# Power.net
KiCad netlist of a schematic drawn in Altium Designer
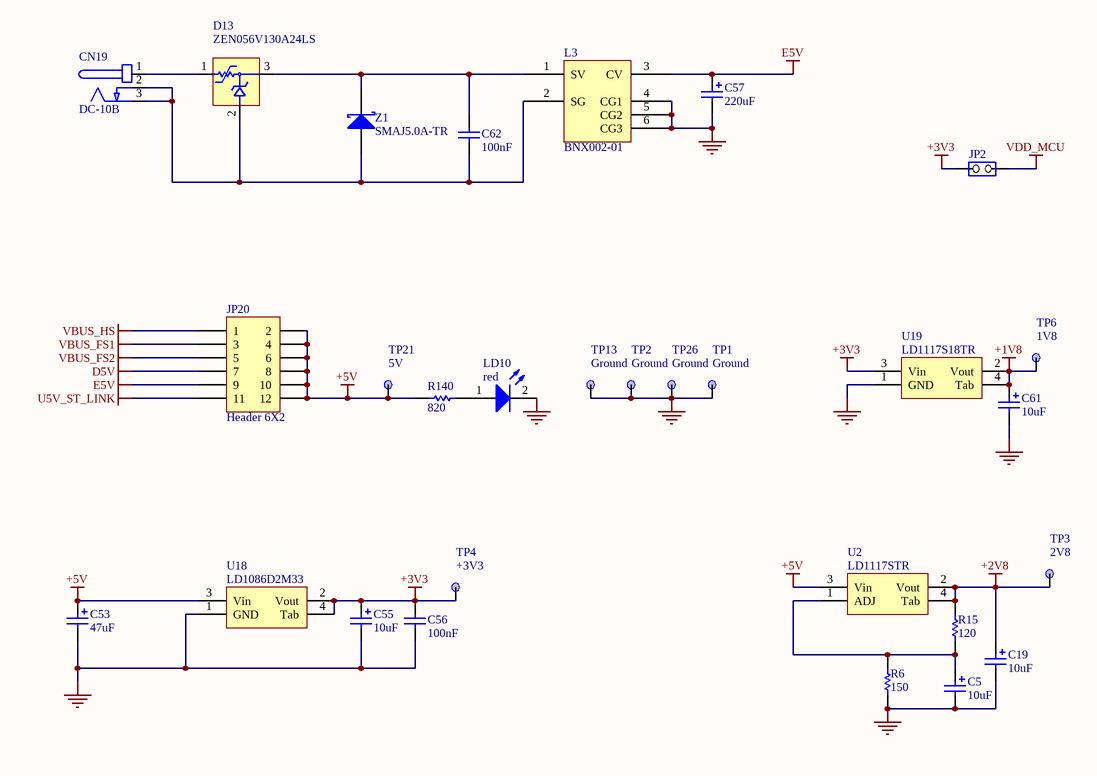
[diagram p0: Power.SchDoc]

(export (version "E")
  (design (tool "Eeschema 10.0.6"))
  (components
    (comp (ref "C5")
      (value "10uF")
      (footprint "TAN-A")
      (description "Polarized Capacitor (Radial)")
      (fields (field (name "PUBLISHER") "Altium Limited"))
      (libsource (lib "Miscellaneous Devices") (part "Cap Pol1"))
    )
    (comp (ref "C19")
      (value "10uF")
      (footprint "TAN-A")
      (description "Polarized Capacitor (Radial)")
      (fields (field (name "PUBLISHER") "Altium Limited"))
      (libsource (lib "Miscellaneous Devices") (part "Cap Pol1"))
    )
    (comp (ref "C53")
      (value "47uF")
      (footprint "CAE_5R3X5R3_H5R4")
      (description "Polarized Capacitor (Radial)")
      (fields (field (name "PUBLISHER") "Altium Limited"))
      (libsource (lib "Miscellaneous Devices") (part "Cap Pol1"))
    )
    (comp (ref "C55")
      (value "10uF")
      (footprint "TAN-A")
      (description "Polarized Capacitor (Radial)")
      (fields (field (name "PUBLISHER") "Altium Limited"))
      (libsource (lib "Miscellaneous Devices") (part "Cap Pol1"))
    )
    (comp (ref "C56")
      (value "100nF")
      (footprint "0603C")
      (description "Capacitor")
      (fields (field (name "PUBLISHER") "Altium Limited"))
      (libsource (lib "Miscellaneous Devices") (part "Cap"))
    )
    (comp (ref "C57")
      (value "220uF")
      (footprint "c310m-6")
      (description "Polarized Capacitor (Radial)")
      (fields (field (name "PUBLISHER") "Altium Limited"))
      (libsource (lib "Miscellaneous Devices") (part "Cap Pol1"))
    )
    (comp (ref "C61")
      (value "10uF")
      (footprint "TAN-A")
      (description "Polarized Capacitor (Radial)")
      (fields (field (name "PUBLISHER") "Altium Limited"))
      (libsource (lib "Miscellaneous Devices") (part "Cap Pol1"))
    )
    (comp (ref "C62")
      (value "100nF")
      (footprint "0603C")
      (description "Capacitor")
      (fields (field (name "PUBLISHER") "Altium Limited"))
      (libsource (lib "Miscellaneous Devices") (part "CAP"))
    )
    (comp (ref "CN19")
      (value "DC-10B")
      (footprint "PWR_JACK_DC10")
      (libsource (lib "STR910_SCHLIB") (part "PJ202A"))
    )
    (comp (ref "D13")
      (value "ZEN056V130A24LS")
      (footprint "TYCO_ZEN056V130A24LS")
      (libsource (lib "STR910_SCHLIB") (part "ZEN056V130A24LS"))
    )
    (comp (ref "JP2") (value "~") (footprint "SIP2") (libsource (lib "*") (part "JP2")))
    (comp (ref "JP20")
      (value "Header 6X2")
      (footprint "HDR_2X6_2R54")
      (description "Header, 6-Pin, Dual row")
      (fields (field (name "PUBLISHER") "Altium Limited"))
      (libsource (lib "mb1045") (part "Header 6X2"))
    )
    (comp (ref "L3")
      (value "BNX002-01")
      (footprint "BNX001")
      (libsource (lib "STR910_SCHLIB") (part "BNX002"))
    )
    (comp (ref "LD10")
      (value "red")
      (footprint "0603D")
      (description "Typical RED, GREEN, YELLOW, AMBER GaAs LED")
      (fields (field (name "PUBLISHER") "Altium Limited"))
      (libsource (lib "Miscellaneous Devices") (part "LED2"))
    )
    (comp (ref "R6")
      (value "150")
      (footprint "0603R")
      (description "Resistor")
      (fields (field (name "PUBLISHER") "Altium Limited"))
      (libsource (lib "Miscellaneous Devices") (part "res1"))
    )
    (comp (ref "R15")
      (value "120")
      (footprint "0603R")
      (description "Resistor")
      (fields (field (name "PUBLISHER") "Altium Limited"))
      (libsource (lib "Miscellaneous Devices") (part "res1"))
    )
    (comp (ref "R140")
      (value "820")
      (footprint "0603R")
      (description "Resistor")
      (fields (field (name "PUBLISHER") "Altium Limited"))
      (libsource (lib "Miscellaneous Devices") (part "res1"))
    )
    (comp (ref "TP1") (value "Ground") (footprint "TP") (libsource (lib "*") (part "TP")))
    (comp (ref "TP2") (value "Ground") (footprint "TP") (libsource (lib "*") (part "TP")))
    (comp (ref "TP3") (value "2V8") (footprint "TP") (libsource (lib "*") (part "TP")))
    (comp (ref "TP4") (value "+3V3") (footprint "TP") (libsource (lib "*") (part "TP")))
    (comp (ref "TP6") (value "1V8") (footprint "TP") (libsource (lib "*") (part "TP")))
    (comp (ref "TP13") (value "Ground") (footprint "TP") (libsource (lib "*") (part "TP")))
    (comp (ref "TP21") (value "5V") (footprint "TP") (libsource (lib "*") (part "TP")))
    (comp (ref "TP26") (value "Ground") (footprint "TP") (libsource (lib "*") (part "TP")))
    (comp (ref "U2") (value "LD1117STR") (footprint "SOT-223") (libsource (lib "MB1219") (part "LD1117STR")))
    (comp (ref "U18")
      (value "LD1086D2M33")
      (footprint "TO263-3")
      (libsource (lib "MB1219") (part "LD1086D2M33"))
    )
    (comp (ref "U19")
      (value "LD1117S18TR")
      (footprint "SOT-223")
      (libsource (lib "MB1219") (part "LD1117S18TR"))
    )
    (comp (ref "Z1")
      (value "SMAJ5.0A-TR")
      (footprint "sma")
      (description "Schottky Diode")
      (fields (field (name "PUBLISHER") "Altium Limited"))
      (libsource (lib "Miscellaneous Devices") (part "D Schottky"))
    )
  )
  (nets
    (net (code "1") (name "+1V8") (class "Default")
      (node (ref "C61") (pin "1") (pinfunction "1_1") (pintype "passive"))
      (node (ref "TP6") (pin "1") (pinfunction "1_1") (pintype "passive"))
      (node (ref "U19") (pin "2") (pinfunction "Vout_2") (pintype "power_in"))
      (node (ref "U19") (pin "4") (pinfunction "Tab_4") (pintype "power_in"))
    )
    (net (code "2") (name "+2V8") (class "Default")
      (node (ref "C19") (pin "1") (pinfunction "1_1") (pintype "passive"))
      (node (ref "R15") (pin "1") (pinfunction "1_1") (pintype "passive"))
      (node (ref "TP3") (pin "1") (pinfunction "1_1") (pintype "passive"))
      (node (ref "U2") (pin "2") (pinfunction "Vout_2") (pintype "power_in"))
      (node (ref "U2") (pin "4") (pinfunction "Tab_4") (pintype "power_in"))
    )
    (net (code "3") (name "+3V3") (class "Default")
      (node (ref "C55") (pin "1") (pinfunction "1_1") (pintype "passive"))
      (node (ref "C56") (pin "1") (pinfunction "1_1") (pintype "passive"))
      (node (ref "JP2") (pin "1") (pinfunction "COMMON_1") (pintype "passive"))
      (node (ref "TP4") (pin "1") (pinfunction "1_1") (pintype "passive"))
      (node (ref "U18") (pin "2") (pinfunction "Vout_2") (pintype "power_in"))
      (node (ref "U18") (pin "4") (pinfunction "Tab_4") (pintype "power_in"))
      (node (ref "U19") (pin "3") (pinfunction "Vin_3") (pintype "power_in"))
    )
    (net (code "4") (name "+5V") (class "Default")
      (node (ref "C53") (pin "1") (pinfunction "1_1") (pintype "passive"))
      (node (ref "JP20") (pin "10") (pinfunction "10_10") (pintype "passive"))
      (node (ref "JP20") (pin "12") (pinfunction "12_12") (pintype "passive"))
      (node (ref "JP20") (pin "2") (pinfunction "2_2") (pintype "passive"))
      (node (ref "JP20") (pin "4") (pinfunction "4_4") (pintype "passive"))
      (node (ref "JP20") (pin "6") (pinfunction "6_6") (pintype "passive"))
      (node (ref "JP20") (pin "8") (pinfunction "8_8") (pintype "passive"))
      (node (ref "R140") (pin "2") (pinfunction "2_2") (pintype "passive"))
      (node (ref "TP21") (pin "1") (pinfunction "1_1") (pintype "passive"))
      (node (ref "U18") (pin "3") (pinfunction "Vin_3") (pintype "power_in"))
      (node (ref "U2") (pin "3") (pinfunction "Vin_3") (pintype "power_in"))
    )
    (net (code "5") (name "D5V") (class "Default")
      (node (ref "JP20") (pin "7") (pinfunction "7_7") (pintype "passive"))
    )
    (net (code "6") (name "E5V") (class "Default")
      (node (ref "C57") (pin "1") (pinfunction "1_1") (pintype "passive"))
      (node (ref "JP20") (pin "9") (pinfunction "9_9") (pintype "passive"))
      (node (ref "L3") (pin "3") (pinfunction "CV_3") (pintype "passive"))
    )
    (net (code "7") (name "GND") (class "Default")
      (node (ref "C19") (pin "2") (pinfunction "2_2") (pintype "passive"))
      (node (ref "C5") (pin "2") (pinfunction "2_2") (pintype "passive"))
      (node (ref "C53") (pin "2") (pinfunction "2_2") (pintype "passive"))
      (node (ref "C55") (pin "2") (pinfunction "2_2") (pintype "passive"))
      (node (ref "C56") (pin "2") (pinfunction "2_2") (pintype "passive"))
      (node (ref "C57") (pin "2") (pinfunction "2_2") (pintype "passive"))
      (node (ref "C61") (pin "2") (pinfunction "2_2") (pintype "passive"))
      (node (ref "L3") (pin "4") (pinfunction "CG1_4") (pintype "passive"))
      (node (ref "L3") (pin "5") (pinfunction "CG2_5") (pintype "passive"))
      (node (ref "L3") (pin "6") (pinfunction "CG3_6") (pintype "passive"))
      (node (ref "LD10") (pin "2") (pinfunction "K_2") (pintype "passive"))
      (node (ref "R6") (pin "2") (pinfunction "2_2") (pintype "passive"))
      (node (ref "TP1") (pin "1") (pinfunction "1_1") (pintype "passive"))
      (node (ref "TP13") (pin "1") (pinfunction "1_1") (pintype "passive"))
      (node (ref "TP2") (pin "1") (pinfunction "1_1") (pintype "passive"))
      (node (ref "TP26") (pin "1") (pinfunction "1_1") (pintype "passive"))
      (node (ref "U18") (pin "1") (pinfunction "GND_1") (pintype "power_in"))
      (node (ref "U19") (pin "1") (pinfunction "GND_1") (pintype "power_in"))
    )
    (net (code "8") (name "Net-(CN19-+)") (class "Default")
      (node (ref "CN19") (pin "1") (pinfunction "+_1") (pintype "passive"))
      (node (ref "D13") (pin "1") (pintype "passive"))
    )
    (net (code "9") (name "Net-(L3-SG)") (class "Default")
      (node (ref "C62") (pin "2") (pinfunction "2_2") (pintype "passive"))
      (node (ref "CN19") (pin "2") (pinfunction "GND_2") (pintype "passive"))
      (node (ref "CN19") (pin "3") (pinfunction "GND_3") (pintype "passive"))
      (node (ref "D13") (pin "2") (pintype "passive"))
      (node (ref "L3") (pin "2") (pinfunction "SG_2") (pintype "passive"))
      (node (ref "Z1") (pin "1") (pinfunction "A_1") (pintype "passive"))
    )
    (net (code "10") (name "Net-(L3-SV)") (class "Default")
      (node (ref "C62") (pin "1") (pinfunction "1_1") (pintype "passive"))
      (node (ref "D13") (pin "3") (pintype "passive"))
      (node (ref "L3") (pin "1") (pinfunction "SV_1") (pintype "passive"))
      (node (ref "Z1") (pin "2") (pinfunction "K_2") (pintype "passive"))
    )
    (net (code "11") (name "Net-(LD10-A)") (class "Default")
      (node (ref "LD10") (pin "1") (pinfunction "A_1") (pintype "passive"))
      (node (ref "R140") (pin "1") (pinfunction "1_1") (pintype "passive"))
    )
    (net (code "12") (name "Net-(U2-ADJ)") (class "Default")
      (node (ref "C5") (pin "1") (pinfunction "1_1") (pintype "passive"))
      (node (ref "R15") (pin "2") (pinfunction "2_2") (pintype "passive"))
      (node (ref "R6") (pin "1") (pinfunction "1_1") (pintype "passive"))
      (node (ref "U2") (pin "1") (pinfunction "ADJ_1") (pintype "passive"))
    )
    (net (code "13") (name "U5V_ST_LINK") (class "Default")
      (node (ref "JP20") (pin "11") (pinfunction "11_11") (pintype "passive"))
    )
    (net (code "14") (name "VBUS_FS1") (class "Default")
      (node (ref "JP20") (pin "3") (pinfunction "3_3") (pintype "passive"))
    )
    (net (code "15") (name "VBUS_FS2") (class "Default")
      (node (ref "JP20") (pin "5") (pinfunction "5_5") (pintype "passive"))
    )
    (net (code "16") (name "VBUS_HS") (class "Default")
      (node (ref "JP20") (pin "1") (pinfunction "1_1") (pintype "passive"))
    )
    (net (code "17") (name "VDD_MCU") (class "Default")
      (node (ref "JP2") (pin "2") (pinfunction "NO_2") (pintype "passive"))
    )
  )
)
